# Optocuplers.net
KiCad netlist of a schematic drawn in Altium Designer
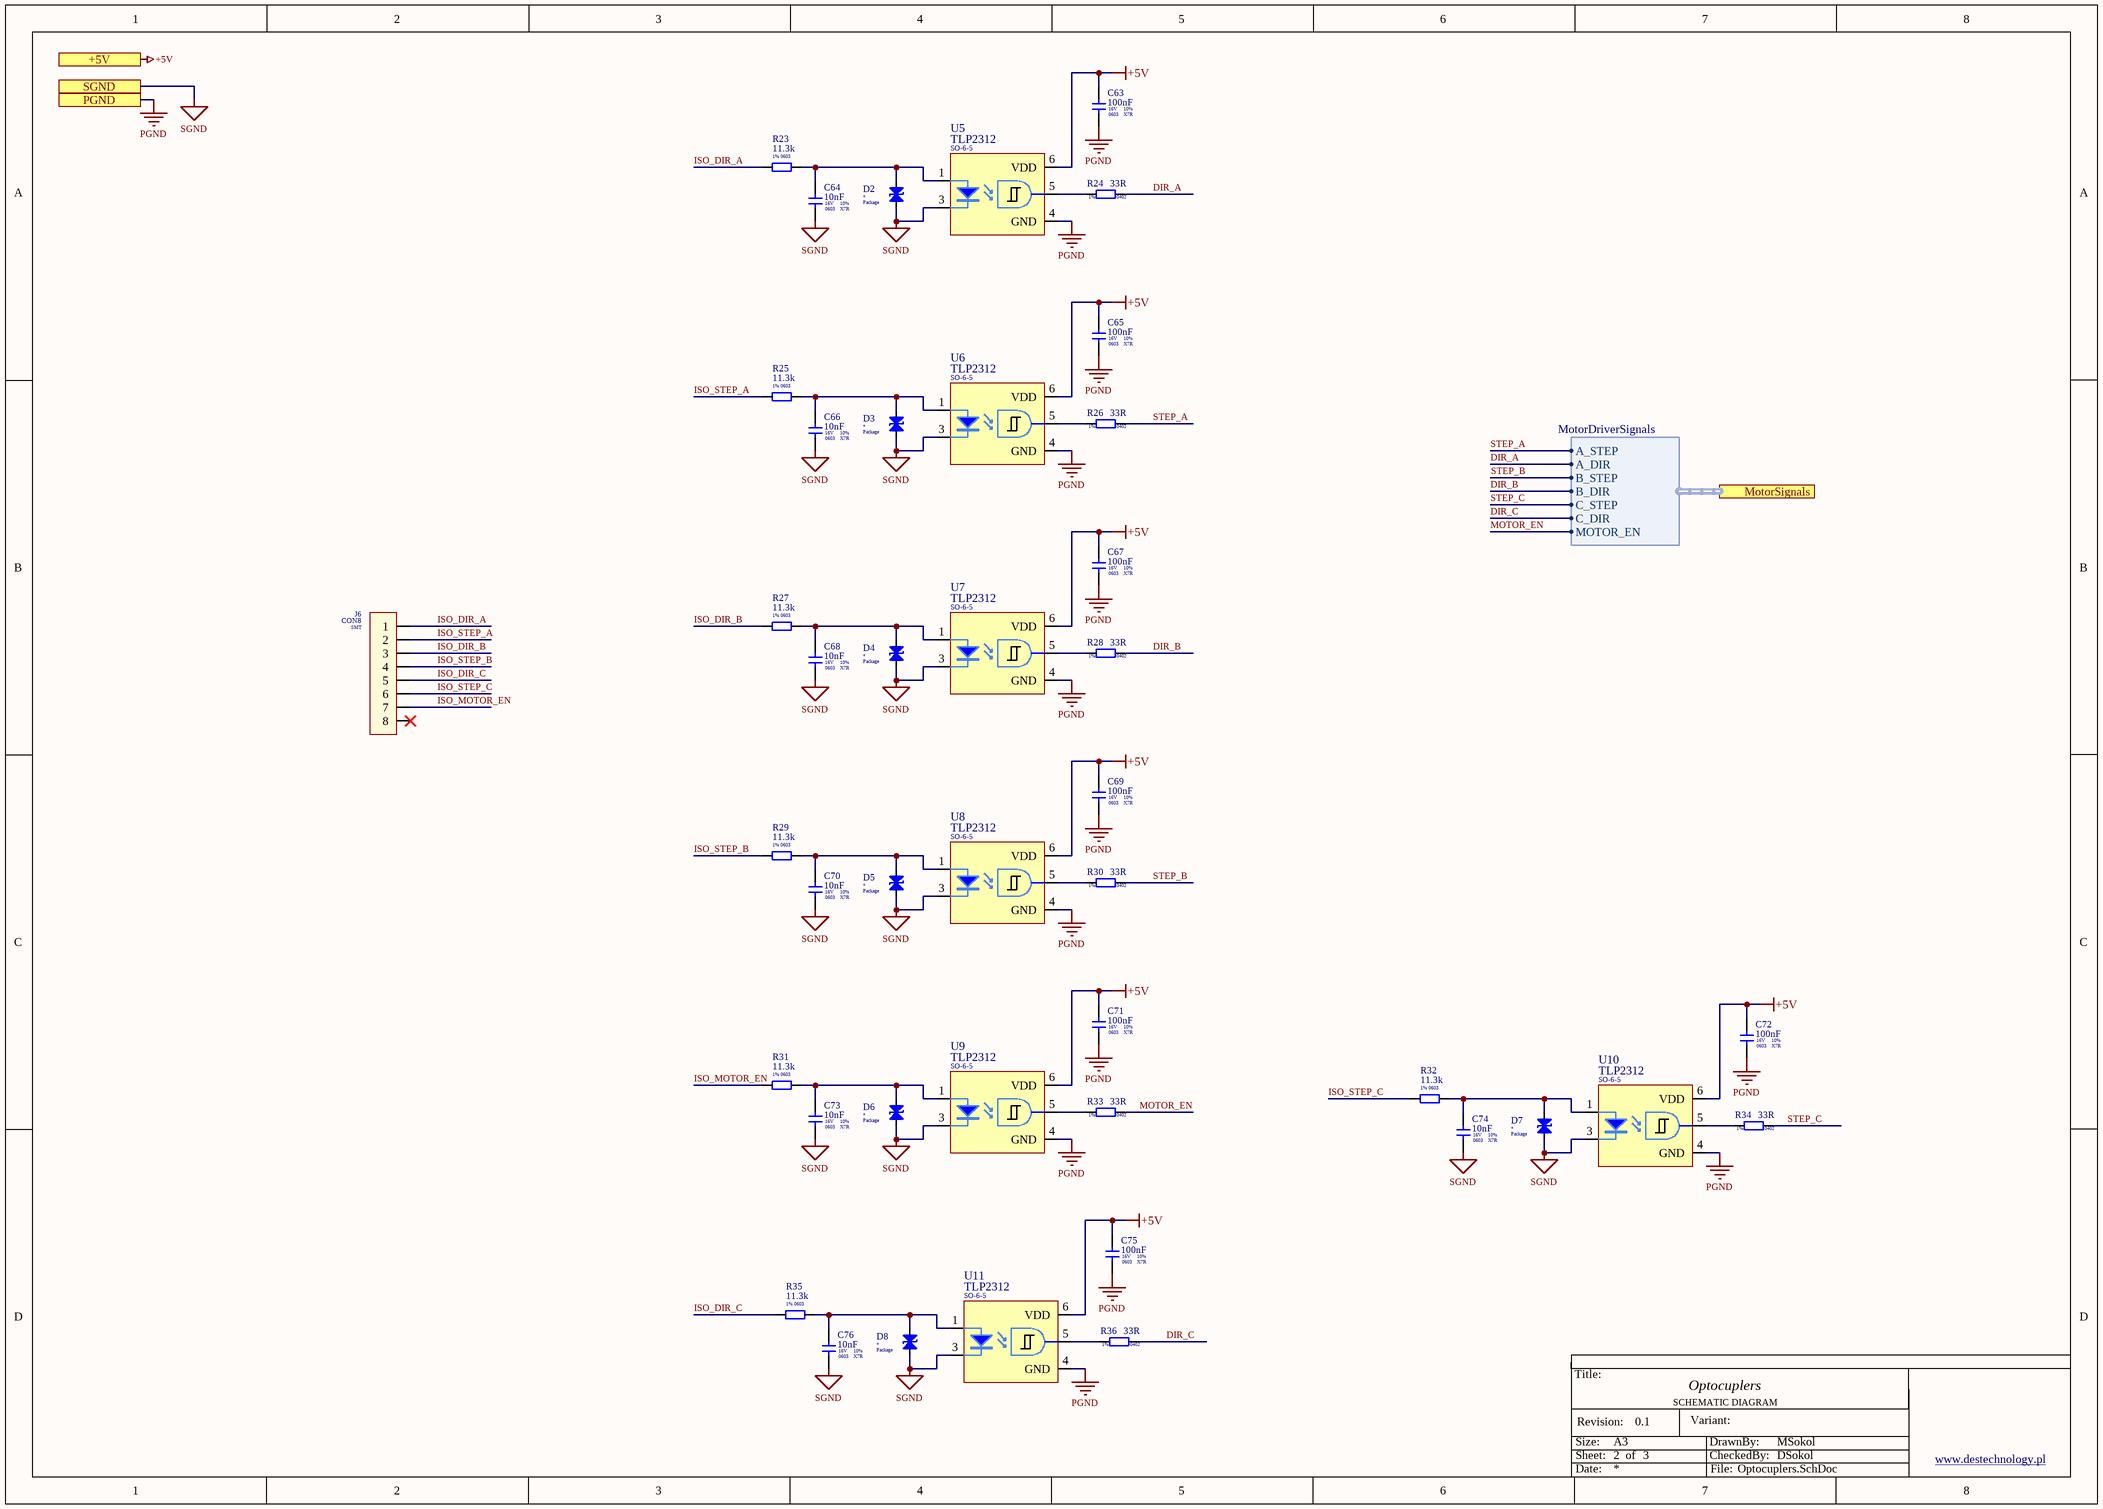
[diagram p0: Optocuplers.SchDoc]

(export (version "E")
  (design (tool "Eeschema 10.0.6"))
  (components
    (comp (ref "C63")
      (value "100nF")
      (footprint "CAPC1608X06M")
      (fields
        (field (name "DIELECTRICTYPE") "X7R")
        (field (name "VOLTAGE") "16V")
        (field (name "TOLERANT") "10%")
        (field (name "PACKAGE") "0603")
        (field (name "Comment") "100nF/16V")
      )
      (libsource (lib "unnamed") (part "C"))
    )
    (comp (ref "C64")
      (value "10nF")
      (footprint "CAPC1608X06M")
      (fields
        (field (name "DIELECTRICTYPE") "X7R")
        (field (name "VOLTAGE") "16V")
        (field (name "TOLERANT") "10%")
        (field (name "PACKAGE") "0603")
        (field (name "Comment") "10nF/16V")
      )
      (libsource (lib "unnamed") (part "C"))
    )
    (comp (ref "C65")
      (value "100nF")
      (footprint "CAPC1608X06M")
      (fields
        (field (name "DIELECTRICTYPE") "X7R")
        (field (name "VOLTAGE") "16V")
        (field (name "TOLERANT") "10%")
        (field (name "PACKAGE") "0603")
        (field (name "Comment") "100nF/16V")
      )
      (libsource (lib "unnamed") (part "C"))
    )
    (comp (ref "C66")
      (value "10nF")
      (footprint "CAPC1608X06M")
      (fields
        (field (name "DIELECTRICTYPE") "X7R")
        (field (name "VOLTAGE") "16V")
        (field (name "TOLERANT") "10%")
        (field (name "PACKAGE") "0603")
        (field (name "Comment") "10nF/16V")
      )
      (libsource (lib "unnamed") (part "C"))
    )
    (comp (ref "C67")
      (value "100nF")
      (footprint "CAPC1608X06M")
      (fields
        (field (name "DIELECTRICTYPE") "X7R")
        (field (name "VOLTAGE") "16V")
        (field (name "TOLERANT") "10%")
        (field (name "PACKAGE") "0603")
        (field (name "Comment") "100nF/16V")
      )
      (libsource (lib "unnamed") (part "C"))
    )
    (comp (ref "C68")
      (value "10nF")
      (footprint "CAPC1608X06M")
      (fields
        (field (name "DIELECTRICTYPE") "X7R")
        (field (name "VOLTAGE") "16V")
        (field (name "TOLERANT") "10%")
        (field (name "PACKAGE") "0603")
        (field (name "Comment") "10nF/16V")
      )
      (libsource (lib "unnamed") (part "C"))
    )
    (comp (ref "C69")
      (value "100nF")
      (footprint "CAPC1608X06M")
      (fields
        (field (name "DIELECTRICTYPE") "X7R")
        (field (name "VOLTAGE") "16V")
        (field (name "TOLERANT") "10%")
        (field (name "PACKAGE") "0603")
        (field (name "Comment") "100nF/16V")
      )
      (libsource (lib "unnamed") (part "C"))
    )
    (comp (ref "C70")
      (value "10nF")
      (footprint "CAPC1608X06M")
      (fields
        (field (name "DIELECTRICTYPE") "X7R")
        (field (name "VOLTAGE") "16V")
        (field (name "TOLERANT") "10%")
        (field (name "PACKAGE") "0603")
        (field (name "Comment") "10nF/16V")
      )
      (libsource (lib "unnamed") (part "C"))
    )
    (comp (ref "C71")
      (value "100nF")
      (footprint "CAPC1608X06M")
      (fields
        (field (name "DIELECTRICTYPE") "X7R")
        (field (name "VOLTAGE") "16V")
        (field (name "TOLERANT") "10%")
        (field (name "PACKAGE") "0603")
        (field (name "Comment") "100nF/16V")
      )
      (libsource (lib "unnamed") (part "C"))
    )
    (comp (ref "C72")
      (value "100nF")
      (footprint "CAPC1608X06M")
      (fields
        (field (name "DIELECTRICTYPE") "X7R")
        (field (name "VOLTAGE") "16V")
        (field (name "TOLERANT") "10%")
        (field (name "PACKAGE") "0603")
        (field (name "Comment") "100nF/16V")
      )
      (libsource (lib "unnamed") (part "C"))
    )
    (comp (ref "C73")
      (value "10nF")
      (footprint "CAPC1608X06M")
      (fields
        (field (name "DIELECTRICTYPE") "X7R")
        (field (name "VOLTAGE") "16V")
        (field (name "TOLERANT") "10%")
        (field (name "PACKAGE") "0603")
        (field (name "Comment") "10nF/16V")
      )
      (libsource (lib "unnamed") (part "C"))
    )
    (comp (ref "C74")
      (value "10nF")
      (footprint "CAPC1608X06M")
      (fields
        (field (name "DIELECTRICTYPE") "X7R")
        (field (name "VOLTAGE") "16V")
        (field (name "TOLERANT") "10%")
        (field (name "PACKAGE") "0603")
        (field (name "Comment") "10nF/16V")
      )
      (libsource (lib "unnamed") (part "C"))
    )
    (comp (ref "C75")
      (value "100nF")
      (footprint "CAPC1608X06M")
      (fields
        (field (name "DIELECTRICTYPE") "X7R")
        (field (name "VOLTAGE") "16V")
        (field (name "TOLERANT") "10%")
        (field (name "PACKAGE") "0603")
        (field (name "Comment") "100nF/16V")
      )
      (libsource (lib "unnamed") (part "C"))
    )
    (comp (ref "C76")
      (value "10nF")
      (footprint "CAPC1608X06M")
      (fields
        (field (name "DIELECTRICTYPE") "X7R")
        (field (name "VOLTAGE") "16V")
        (field (name "TOLERANT") "10%")
        (field (name "PACKAGE") "0603")
        (field (name "Comment") "10nF/16V")
      )
      (libsource (lib "unnamed") (part "C"))
    )
    (comp (ref "D2")
      (value "*")
      (footprint "SODFL250X90-2N")
      (fields (field (name "PACKAGE") "Package") (field (name "ALTIUM_VALUE") "*"))
      (libsource (lib "unnamed") (part "D_TRANSIL1"))
    )
    (comp (ref "D3")
      (value "*")
      (footprint "SODFL250X90-2N")
      (fields (field (name "PACKAGE") "Package") (field (name "ALTIUM_VALUE") "*"))
      (libsource (lib "unnamed") (part "D_TRANSIL1"))
    )
    (comp (ref "D4")
      (value "*")
      (footprint "SODFL250X90-2N")
      (fields (field (name "PACKAGE") "Package") (field (name "ALTIUM_VALUE") "*"))
      (libsource (lib "unnamed") (part "D_TRANSIL1"))
    )
    (comp (ref "D5")
      (value "*")
      (footprint "SODFL250X90-2N")
      (fields (field (name "PACKAGE") "Package") (field (name "ALTIUM_VALUE") "*"))
      (libsource (lib "unnamed") (part "D_TRANSIL1"))
    )
    (comp (ref "D6")
      (value "*")
      (footprint "SODFL250X90-2N")
      (fields (field (name "PACKAGE") "Package") (field (name "ALTIUM_VALUE") "*"))
      (libsource (lib "unnamed") (part "D_TRANSIL1"))
    )
    (comp (ref "D7")
      (value "*")
      (footprint "SODFL250X90-2N")
      (fields (field (name "PACKAGE") "Package") (field (name "ALTIUM_VALUE") "*"))
      (libsource (lib "unnamed") (part "D_TRANSIL1"))
    )
    (comp (ref "D8")
      (value "*")
      (footprint "SODFL250X90-2N")
      (fields (field (name "PACKAGE") "Package") (field (name "ALTIUM_VALUE") "*"))
      (libsource (lib "unnamed") (part "D_TRANSIL1"))
    )
    (comp (ref "J6")
      (value "CON8")
      (footprint "B8B-PH-K-S")
      (fields (field (name "PACKAGE") "SMT"))
      (libsource (lib "unnamed") (part "CON_8PIN"))
    )
    (comp (ref "R23")
      (value "11.3k")
      (footprint "RESC1608X06M")
      (fields
        (field (name "PACKAGE") "0603")
        (field (name "TOLERANCE") "1%")
        (field (name "Comment") "11.3k 1%")
      )
      (libsource (lib "unnamed") (part "R"))
    )
    (comp (ref "R24")
      (value "33R")
      (footprint "RESC1005X03L")
      (fields
        (field (name "PACKAGE") "0402")
        (field (name "TOLERANCE") "1%")
        (field (name "Comment") "33R 1%")
      )
      (libsource (lib "") (part "R_1"))
    )
    (comp (ref "R25")
      (value "11.3k")
      (footprint "RESC1608X06M")
      (fields
        (field (name "PACKAGE") "0603")
        (field (name "TOLERANCE") "1%")
        (field (name "Comment") "11.3k 1%")
      )
      (libsource (lib "unnamed") (part "R"))
    )
    (comp (ref "R26")
      (value "33R")
      (footprint "RESC1005X03L")
      (fields
        (field (name "PACKAGE") "0402")
        (field (name "TOLERANCE") "1%")
        (field (name "Comment") "33R 1%")
      )
      (libsource (lib "") (part "R_1"))
    )
    (comp (ref "R27")
      (value "11.3k")
      (footprint "RESC1608X06M")
      (fields
        (field (name "PACKAGE") "0603")
        (field (name "TOLERANCE") "1%")
        (field (name "Comment") "11.3k 1%")
      )
      (libsource (lib "unnamed") (part "R"))
    )
    (comp (ref "R28")
      (value "33R")
      (footprint "RESC1005X03L")
      (fields
        (field (name "PACKAGE") "0402")
        (field (name "TOLERANCE") "1%")
        (field (name "Comment") "33R 1%")
      )
      (libsource (lib "") (part "R_1"))
    )
    (comp (ref "R29")
      (value "11.3k")
      (footprint "RESC1608X06M")
      (fields
        (field (name "PACKAGE") "0603")
        (field (name "TOLERANCE") "1%")
        (field (name "Comment") "11.3k 1%")
      )
      (libsource (lib "unnamed") (part "R"))
    )
    (comp (ref "R30")
      (value "33R")
      (footprint "RESC1005X03L")
      (fields
        (field (name "PACKAGE") "0402")
        (field (name "TOLERANCE") "1%")
        (field (name "Comment") "33R 1%")
      )
      (libsource (lib "") (part "R_1"))
    )
    (comp (ref "R31")
      (value "11.3k")
      (footprint "RESC1608X06M")
      (fields
        (field (name "PACKAGE") "0603")
        (field (name "TOLERANCE") "1%")
        (field (name "Comment") "11.3k 1%")
      )
      (libsource (lib "unnamed") (part "R"))
    )
    (comp (ref "R32")
      (value "11.3k")
      (footprint "RESC1608X06N")
      (fields
        (field (name "PACKAGE") "0603")
        (field (name "TOLERANCE") "1%")
        (field (name "Comment") "11.3k 1%")
      )
      (libsource (lib "unnamed") (part "R"))
    )
    (comp (ref "R33")
      (value "33R")
      (footprint "RESC1005X03L")
      (fields
        (field (name "PACKAGE") "0402")
        (field (name "TOLERANCE") "1%")
        (field (name "Comment") "33R 1%")
      )
      (libsource (lib "") (part "R_1"))
    )
    (comp (ref "R34")
      (value "33R")
      (footprint "RESC1005X03L")
      (fields
        (field (name "PACKAGE") "0402")
        (field (name "TOLERANCE") "1%")
        (field (name "Comment") "33R 1%")
      )
      (libsource (lib "") (part "R_1"))
    )
    (comp (ref "R35")
      (value "11.3k")
      (footprint "RESC1608X06M")
      (fields
        (field (name "PACKAGE") "0603")
        (field (name "TOLERANCE") "1%")
        (field (name "Comment") "11.3k 1%")
      )
      (libsource (lib "unnamed") (part "R"))
    )
    (comp (ref "R36")
      (value "33R")
      (footprint "RESC1005X03L")
      (fields
        (field (name "PACKAGE") "0402")
        (field (name "TOLERANCE") "1%")
        (field (name "Comment") "33R 1%")
      )
      (libsource (lib "") (part "R_1"))
    )
    (comp (ref "U5")
      (value "TLP2312")
      (footprint "SO-6-5")
      (description "High Speed Optocouplers High speed photocoupler; 5pin SO6")
      (fields (field (name "MANUFACTURER") "Toshiba") (field (name "CASE") "SO-6-5"))
      (libsource (lib "unnamed") (part "TLP2312"))
    )
    (comp (ref "U6")
      (value "TLP2312")
      (footprint "SO-6-5")
      (description "High Speed Optocouplers High speed photocoupler; 5pin SO6")
      (fields (field (name "MANUFACTURER") "Toshiba") (field (name "CASE") "SO-6-5"))
      (libsource (lib "unnamed") (part "TLP2312"))
    )
    (comp (ref "U7")
      (value "TLP2312")
      (footprint "SO-6-5")
      (description "High Speed Optocouplers High speed photocoupler; 5pin SO6")
      (fields (field (name "MANUFACTURER") "Toshiba") (field (name "CASE") "SO-6-5"))
      (libsource (lib "unnamed") (part "TLP2312"))
    )
    (comp (ref "U8")
      (value "TLP2312")
      (footprint "SO-6-5")
      (description "High Speed Optocouplers High speed photocoupler; 5pin SO6")
      (fields (field (name "MANUFACTURER") "Toshiba") (field (name "CASE") "SO-6-5"))
      (libsource (lib "unnamed") (part "TLP2312"))
    )
    (comp (ref "U9")
      (value "TLP2312")
      (footprint "SO-6-5")
      (description "High Speed Optocouplers High speed photocoupler; 5pin SO6")
      (fields (field (name "MANUFACTURER") "Toshiba") (field (name "CASE") "SO-6-5"))
      (libsource (lib "unnamed") (part "TLP2312"))
    )
    (comp (ref "U10")
      (value "TLP2312")
      (footprint "SO-6-5")
      (description "High Speed Optocouplers High speed photocoupler; 5pin SO6")
      (fields (field (name "MANUFACTURER") "Toshiba") (field (name "CASE") "SO-6-5"))
      (libsource (lib "unnamed") (part "TLP2312"))
    )
    (comp (ref "U11")
      (value "TLP2312")
      (footprint "SO-6-5")
      (description "High Speed Optocouplers High speed photocoupler; 5pin SO6")
      (fields (field (name "MANUFACTURER") "Toshiba") (field (name "CASE") "SO-6-5"))
      (libsource (lib "unnamed") (part "TLP2312"))
    )
  )
  (nets
    (net (code "2") (name "+5V") (class "Default")
      (node (ref "C63") (pin "2") (pinfunction "2_2") (pintype "passive"))
      (node (ref "C65") (pin "2") (pinfunction "2_2") (pintype "passive"))
      (node (ref "C67") (pin "2") (pinfunction "2_2") (pintype "passive"))
      (node (ref "C69") (pin "2") (pinfunction "2_2") (pintype "passive"))
      (node (ref "C71") (pin "2") (pinfunction "2_2") (pintype "passive"))
      (node (ref "C72") (pin "2") (pinfunction "2_2") (pintype "passive"))
      (node (ref "C75") (pin "2") (pinfunction "2_2") (pintype "passive"))
      (node (ref "U10") (pin "6") (pinfunction "VDD_6") (pintype "power_in"))
      (node (ref "U11") (pin "6") (pinfunction "VDD_6") (pintype "power_in"))
      (node (ref "U5") (pin "6") (pinfunction "VDD_6") (pintype "power_in"))
      (node (ref "U6") (pin "6") (pinfunction "VDD_6") (pintype "power_in"))
      (node (ref "U7") (pin "6") (pinfunction "VDD_6") (pintype "power_in"))
      (node (ref "U8") (pin "6") (pinfunction "VDD_6") (pintype "power_in"))
      (node (ref "U9") (pin "6") (pinfunction "VDD_6") (pintype "power_in"))
    )
    (net (code "4") (name "/DIR_A") (class "Default")
      (node (ref "R24") (pin "1") (pinfunction "1_1") (pintype "passive"))
    )
    (net (code "5") (name "/DIR_B") (class "Default")
      (node (ref "R28") (pin "1") (pinfunction "1_1") (pintype "passive"))
    )
    (net (code "6") (name "/DIR_C") (class "Default")
      (node (ref "R36") (pin "1") (pinfunction "1_1") (pintype "passive"))
    )
    (net (code "7") (name "/ISO_DIR_A") (class "Default")
      (node (ref "J6") (pin "1") (pinfunction "1_1") (pintype "passive"))
      (node (ref "R23") (pin "1") (pinfunction "1_1") (pintype "passive"))
    )
    (net (code "8") (name "/ISO_DIR_B") (class "Default")
      (node (ref "J6") (pin "3") (pinfunction "3_3") (pintype "passive"))
      (node (ref "R27") (pin "1") (pinfunction "1_1") (pintype "passive"))
    )
    (net (code "9") (name "/ISO_DIR_C") (class "Default")
      (node (ref "J6") (pin "5") (pinfunction "5_5") (pintype "passive"))
      (node (ref "R35") (pin "1") (pinfunction "1_1") (pintype "passive"))
    )
    (net (code "10") (name "/ISO_MOTOR_EN") (class "Default")
      (node (ref "J6") (pin "7") (pinfunction "7_7") (pintype "passive"))
      (node (ref "R31") (pin "1") (pinfunction "1_1") (pintype "passive"))
    )
    (net (code "11") (name "/ISO_STEP_A") (class "Default")
      (node (ref "J6") (pin "2") (pinfunction "2_2") (pintype "passive"))
      (node (ref "R25") (pin "1") (pinfunction "1_1") (pintype "passive"))
    )
    (net (code "12") (name "/ISO_STEP_B") (class "Default")
      (node (ref "J6") (pin "4") (pinfunction "4_4") (pintype "passive"))
      (node (ref "R29") (pin "1") (pinfunction "1_1") (pintype "passive"))
    )
    (net (code "13") (name "/ISO_STEP_C") (class "Default")
      (node (ref "J6") (pin "6") (pinfunction "6_6") (pintype "passive"))
      (node (ref "R32") (pin "1") (pinfunction "1_1") (pintype "passive"))
    )
    (net (code "14") (name "/MOTOR_EN") (class "Default")
      (node (ref "R33") (pin "1") (pinfunction "1_1") (pintype "passive"))
    )
    (net (code "15") (name "/STEP_A") (class "Default")
      (node (ref "R26") (pin "1") (pinfunction "1_1") (pintype "passive"))
    )
    (net (code "16") (name "/STEP_B") (class "Default")
      (node (ref "R30") (pin "1") (pinfunction "1_1") (pintype "passive"))
    )
    (net (code "17") (name "/STEP_C") (class "Default")
      (node (ref "R34") (pin "1") (pinfunction "1_1") (pintype "passive"))
    )
    (net (code "19") (name "Net-(D2-K)") (class "Default")
      (node (ref "C64") (pin "2") (pinfunction "2_2") (pintype "passive"))
      (node (ref "D2") (pin "2") (pinfunction "K_2") (pintype "passive"))
      (node (ref "R23") (pin "2") (pinfunction "2_2") (pintype "passive"))
      (node (ref "U5") (pin "1") (pinfunction "A_1") (pintype "passive"))
    )
    (net (code "20") (name "Net-(D3-K)") (class "Default")
      (node (ref "C66") (pin "2") (pinfunction "2_2") (pintype "passive"))
      (node (ref "D3") (pin "2") (pinfunction "K_2") (pintype "passive"))
      (node (ref "R25") (pin "2") (pinfunction "2_2") (pintype "passive"))
      (node (ref "U6") (pin "1") (pinfunction "A_1") (pintype "passive"))
    )
    (net (code "21") (name "Net-(D4-K)") (class "Default")
      (node (ref "C68") (pin "2") (pinfunction "2_2") (pintype "passive"))
      (node (ref "D4") (pin "2") (pinfunction "K_2") (pintype "passive"))
      (node (ref "R27") (pin "2") (pinfunction "2_2") (pintype "passive"))
      (node (ref "U7") (pin "1") (pinfunction "A_1") (pintype "passive"))
    )
    (net (code "22") (name "Net-(D5-K)") (class "Default")
      (node (ref "C70") (pin "2") (pinfunction "2_2") (pintype "passive"))
      (node (ref "D5") (pin "2") (pinfunction "K_2") (pintype "passive"))
      (node (ref "R29") (pin "2") (pinfunction "2_2") (pintype "passive"))
      (node (ref "U8") (pin "1") (pinfunction "A_1") (pintype "passive"))
    )
    (net (code "23") (name "Net-(D6-K)") (class "Default")
      (node (ref "C73") (pin "2") (pinfunction "2_2") (pintype "passive"))
      (node (ref "D6") (pin "2") (pinfunction "K_2") (pintype "passive"))
      (node (ref "R31") (pin "2") (pinfunction "2_2") (pintype "passive"))
      (node (ref "U9") (pin "1") (pinfunction "A_1") (pintype "passive"))
    )
    (net (code "24") (name "Net-(D7-K)") (class "Default")
      (node (ref "C74") (pin "2") (pinfunction "2_2") (pintype "passive"))
      (node (ref "D7") (pin "2") (pinfunction "K_2") (pintype "passive"))
      (node (ref "R32") (pin "2") (pinfunction "2_2") (pintype "passive"))
      (node (ref "U10") (pin "1") (pinfunction "A_1") (pintype "passive"))
    )
    (net (code "25") (name "Net-(D8-K)") (class "Default")
      (node (ref "C76") (pin "2") (pinfunction "2_2") (pintype "passive"))
      (node (ref "D8") (pin "2") (pinfunction "K_2") (pintype "passive"))
      (node (ref "R35") (pin "2") (pinfunction "2_2") (pintype "passive"))
      (node (ref "U11") (pin "1") (pinfunction "A_1") (pintype "passive"))
    )
    (net (code "26") (name "Net-(U5-Vo)") (class "Default")
      (node (ref "R24") (pin "2") (pinfunction "2_2") (pintype "passive"))
      (node (ref "U5") (pin "5") (pinfunction "Vo_5") (pintype "power_in"))
    )
    (net (code "27") (name "Net-(U6-Vo)") (class "Default")
      (node (ref "R26") (pin "2") (pinfunction "2_2") (pintype "passive"))
      (node (ref "U6") (pin "5") (pinfunction "Vo_5") (pintype "power_in"))
    )
    (net (code "28") (name "Net-(U7-Vo)") (class "Default")
      (node (ref "R28") (pin "2") (pinfunction "2_2") (pintype "passive"))
      (node (ref "U7") (pin "5") (pinfunction "Vo_5") (pintype "power_in"))
    )
    (net (code "29") (name "Net-(U8-Vo)") (class "Default")
      (node (ref "R30") (pin "2") (pinfunction "2_2") (pintype "passive"))
      (node (ref "U8") (pin "5") (pinfunction "Vo_5") (pintype "power_in"))
    )
    (net (code "30") (name "Net-(U9-Vo)") (class "Default")
      (node (ref "R33") (pin "2") (pinfunction "2_2") (pintype "passive"))
      (node (ref "U9") (pin "5") (pinfunction "Vo_5") (pintype "power_in"))
    )
    (net (code "31") (name "Net-(U10-Vo)") (class "Default")
      (node (ref "R34") (pin "2") (pinfunction "2_2") (pintype "passive"))
      (node (ref "U10") (pin "5") (pinfunction "Vo_5") (pintype "power_in"))
    )
    (net (code "32") (name "Net-(U11-Vo)") (class "Default")
      (node (ref "R36") (pin "2") (pinfunction "2_2") (pintype "passive"))
      (node (ref "U11") (pin "5") (pinfunction "Vo_5") (pintype "power_in"))
    )
    (net (code "33") (name "PGND") (class "Default")
      (node (ref "C63") (pin "1") (pinfunction "1_1") (pintype "passive"))
      (node (ref "C65") (pin "1") (pinfunction "1_1") (pintype "passive"))
      (node (ref "C67") (pin "1") (pinfunction "1_1") (pintype "passive"))
      (node (ref "C69") (pin "1") (pinfunction "1_1") (pintype "passive"))
      (node (ref "C71") (pin "1") (pinfunction "1_1") (pintype "passive"))
      (node (ref "C72") (pin "1") (pinfunction "1_1") (pintype "passive"))
      (node (ref "C75") (pin "1") (pinfunction "1_1") (pintype "passive"))
      (node (ref "U10") (pin "4") (pinfunction "GND_4") (pintype "power_in"))
      (node (ref "U11") (pin "4") (pinfunction "GND_4") (pintype "power_in"))
      (node (ref "U5") (pin "4") (pinfunction "GND_4") (pintype "power_in"))
      (node (ref "U6") (pin "4") (pinfunction "GND_4") (pintype "power_in"))
      (node (ref "U7") (pin "4") (pinfunction "GND_4") (pintype "power_in"))
      (node (ref "U8") (pin "4") (pinfunction "GND_4") (pintype "power_in"))
      (node (ref "U9") (pin "4") (pinfunction "GND_4") (pintype "power_in"))
    )
    (net (code "34") (name "SGND") (class "Default")
      (node (ref "C64") (pin "1") (pinfunction "1_1") (pintype "passive"))
      (node (ref "C66") (pin "1") (pinfunction "1_1") (pintype "passive"))
      (node (ref "C68") (pin "1") (pinfunction "1_1") (pintype "passive"))
      (node (ref "C70") (pin "1") (pinfunction "1_1") (pintype "passive"))
      (node (ref "C73") (pin "1") (pinfunction "1_1") (pintype "passive"))
      (node (ref "C74") (pin "1") (pinfunction "1_1") (pintype "passive"))
      (node (ref "C76") (pin "1") (pinfunction "1_1") (pintype "passive"))
      (node (ref "D2") (pin "1") (pinfunction "A_1") (pintype "passive"))
      (node (ref "D3") (pin "1") (pinfunction "A_1") (pintype "passive"))
      (node (ref "D4") (pin "1") (pinfunction "A_1") (pintype "passive"))
      (node (ref "D5") (pin "1") (pinfunction "A_1") (pintype "passive"))
      (node (ref "D6") (pin "1") (pinfunction "A_1") (pintype "passive"))
      (node (ref "D7") (pin "1") (pinfunction "A_1") (pintype "passive"))
      (node (ref "D8") (pin "1") (pinfunction "A_1") (pintype "passive"))
      (node (ref "U10") (pin "3") (pinfunction "K_3") (pintype "passive"))
      (node (ref "U11") (pin "3") (pinfunction "K_3") (pintype "passive"))
      (node (ref "U5") (pin "3") (pinfunction "K_3") (pintype "passive"))
      (node (ref "U6") (pin "3") (pinfunction "K_3") (pintype "passive"))
      (node (ref "U7") (pin "3") (pinfunction "K_3") (pintype "passive"))
      (node (ref "U8") (pin "3") (pinfunction "K_3") (pintype "passive"))
      (node (ref "U9") (pin "3") (pinfunction "K_3") (pintype "passive"))
    )
    (net (code "35") (name "unconnected-(J6-Pad8)") (class "Default")
      (node (ref "J6") (pin "8") (pinfunction "8_8") (pintype "passive+no_connect"))
    )
  )
)
